# schema_Light_system.net
KiCad netlist of a schematic drawn in EAGLE
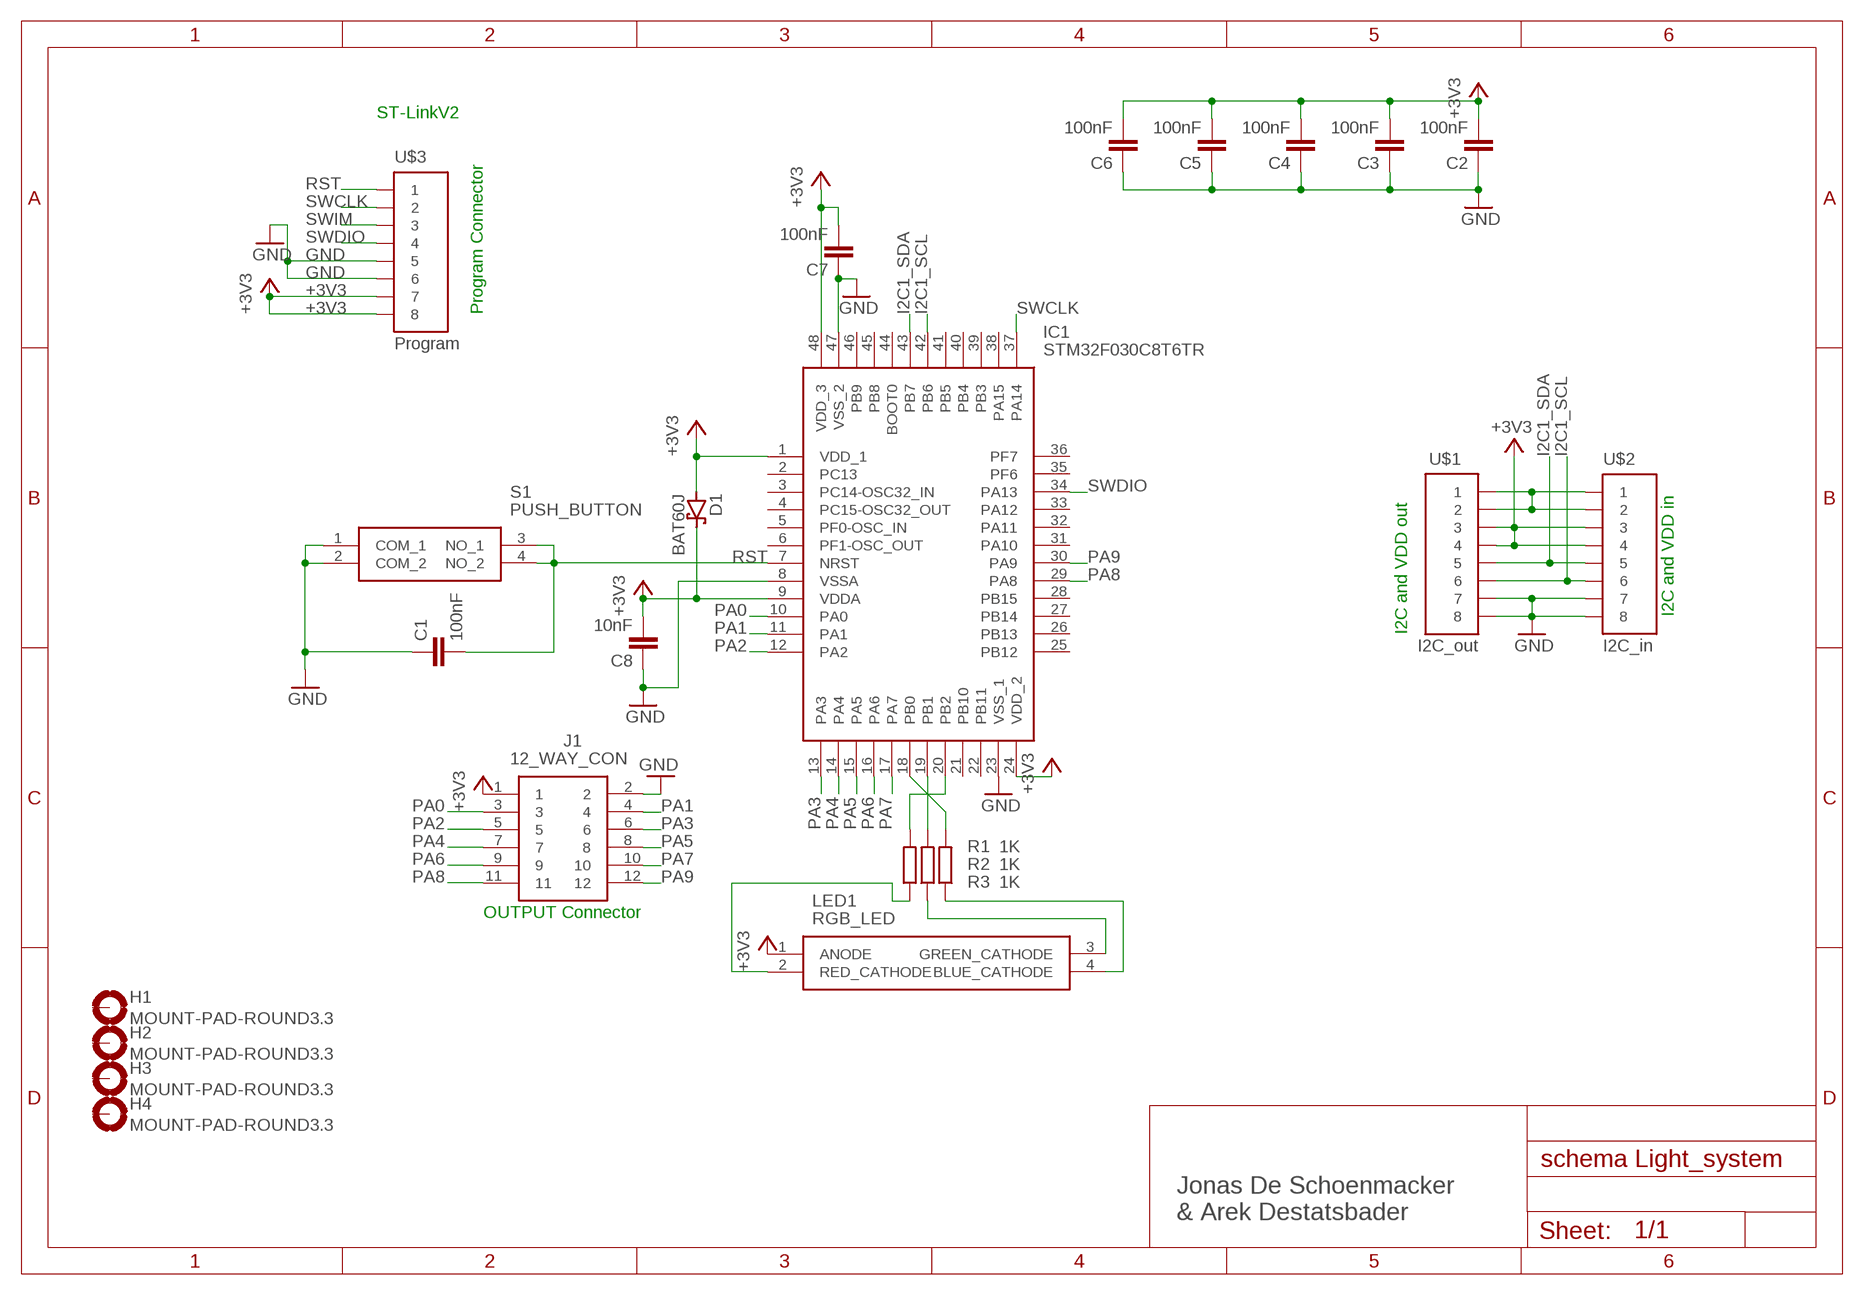
[diagram p0: schematic, sheet 1]

(export (version "E")
  (design (tool "Eeschema 10.0.6"))
  (components
    (comp (ref "C1")
      (value "100nF")
      (footprint "eagle-import:C1206")
      (libsource (lib "eagle-import") (part "C-EUC1206"))
    )
    (comp (ref "C2")
      (value "100nF")
      (footprint "eagle-import:C1206")
      (libsource (lib "eagle-import") (part "C-EUC1206"))
    )
    (comp (ref "C3")
      (value "100nF")
      (footprint "eagle-import:C1206")
      (libsource (lib "eagle-import") (part "C-EUC1206"))
    )
    (comp (ref "C4")
      (value "100nF")
      (footprint "eagle-import:C1206")
      (libsource (lib "eagle-import") (part "C-EUC1206"))
    )
    (comp (ref "C5")
      (value "100nF")
      (footprint "eagle-import:C1206")
      (libsource (lib "eagle-import") (part "C-EUC1206"))
    )
    (comp (ref "C6")
      (value "100nF")
      (footprint "eagle-import:C1206")
      (libsource (lib "eagle-import") (part "C-EUC1206"))
    )
    (comp (ref "C7")
      (value "100nF")
      (footprint "eagle-import:C1206")
      (libsource (lib "eagle-import") (part "C-EUC1206"))
    )
    (comp (ref "C8")
      (value "10nF")
      (footprint "eagle-import:C1206")
      (libsource (lib "eagle-import") (part "C-EUC1206"))
    )
    (comp (ref "D1")
      (value "BAT60J")
      (footprint "eagle-import:SOD323_ST")
      (libsource (lib "eagle-import") (part "BAT60J"))
    )
    (comp (ref "H1")
      (value "MOUNT-PAD-ROUND3.3")
      (footprint "eagle-import:3,3-PAD")
      (libsource (lib "eagle-import") (part "MOUNT-PAD-ROUND3.3"))
    )
    (comp (ref "H2")
      (value "MOUNT-PAD-ROUND3.3")
      (footprint "eagle-import:3,3-PAD")
      (libsource (lib "eagle-import") (part "MOUNT-PAD-ROUND3.3"))
    )
    (comp (ref "H3")
      (value "MOUNT-PAD-ROUND3.3")
      (footprint "eagle-import:3,3-PAD")
      (libsource (lib "eagle-import") (part "MOUNT-PAD-ROUND3.3"))
    )
    (comp (ref "H4")
      (value "MOUNT-PAD-ROUND3.3")
      (footprint "eagle-import:3,3-PAD")
      (libsource (lib "eagle-import") (part "MOUNT-PAD-ROUND3.3"))
    )
    (comp (ref "IC1")
      (value "STM32F030C8T6TR")
      (footprint "eagle-import:QFP50P900X900X160-48N")
      (fields (field (name "MOUSER_PART_NUMBER") "511-STM32F030C8T6TR"))
      (libsource (lib "eagle-import") (part "STM32F030C8T6TR"))
    )
    (comp (ref "J1")
      (value "12_WAY_CON")
      (footprint "eagle-import:1990106")
      (fields
        (field (name "MANUFACTURER_PART_NUMBER") "1990106")
        (field (name "MOUSER_PART_NUMBER") "651-1990106")
      )
      (libsource (lib "eagle-import") (part "12_WAY_CON"))
    )
    (comp (ref "LED1")
      (value "RGB_LED")
      (footprint "eagle-import:ASMBKTF00A306")
      (fields
        (field (name "MANUFACTURER_PART_NUMBER") "ASMB-KTF0-0A306")
        (field (name "MOUSER_PART_NUMBER") "630-ASMB-KTF0-0A306")
      )
      (libsource (lib "eagle-import") (part "RGB_LED"))
    )
    (comp (ref "R1")
      (value "1K")
      (footprint "eagle-import:R1206")
      (libsource (lib "eagle-import") (part "R-EU_R1206"))
    )
    (comp (ref "R2")
      (value "1K")
      (footprint "eagle-import:R1206")
      (libsource (lib "eagle-import") (part "R-EU_R1206"))
    )
    (comp (ref "R3")
      (value "1K")
      (footprint "eagle-import:R1206")
      (libsource (lib "eagle-import") (part "R-EU_R1206"))
    )
    (comp (ref "S1")
      (value "PUSH_BUTTON")
      (footprint "eagle-import:LL3301FF065QJ")
      (fields
        (field (name "MANUFACTURER_PART_NUMBER") "LL3301FF065QJ")
        (field (name "MOUSER_PART_NUMBER") "612-LL3301FF065QJ")
      )
      (libsource (lib "eagle-import") (part "PUSH_BUTTON"))
    )
    (comp (ref "U$1")
      (value "I2C_out")
      (footprint "eagle-import:MA04-2")
      (libsource (lib "eagle-import") (part "MODULARCONNECTOR"))
    )
    (comp (ref "U$2")
      (value "I2C_in")
      (footprint "eagle-import:MA04-2")
      (libsource (lib "eagle-import") (part "MODULARCONNECTOR"))
    )
    (comp (ref "U$3")
      (value "Program")
      (footprint "eagle-import:MA04-2")
      (libsource (lib "eagle-import") (part "MODULARCONNECTOR"))
    )
  )
  (nets
    (net (code "1") (name "+3V3") (class "Default")
      (node (ref "C2") (pin "2") (pinfunction "2_2") (pintype "passive"))
      (node (ref "C3") (pin "2") (pinfunction "2_2") (pintype "passive"))
      (node (ref "C4") (pin "2") (pinfunction "2_2") (pintype "passive"))
      (node (ref "C5") (pin "2") (pinfunction "2_2") (pintype "passive"))
      (node (ref "C6") (pin "2") (pinfunction "2_2") (pintype "passive"))
      (node (ref "C7") (pin "2") (pinfunction "2_2") (pintype "passive"))
      (node (ref "C8") (pin "2") (pinfunction "2_2") (pintype "passive"))
      (node (ref "D1") (pin "A") (pinfunction "A_A") (pintype "passive"))
      (node (ref "D1") (pin "C") (pinfunction "C_C") (pintype "passive"))
      (node (ref "IC1") (pin "1") (pinfunction "VDD_1_1") (pintype "power_in"))
      (node (ref "IC1") (pin "24") (pinfunction "VDD_2_24") (pintype "power_in"))
      (node (ref "IC1") (pin "48") (pinfunction "VDD_3_48") (pintype "power_in"))
      (node (ref "IC1") (pin "9") (pinfunction "VDDA_9") (pintype "power_in"))
      (node (ref "J1") (pin "1") (pinfunction "1_1") (pintype "bidirectional"))
      (node (ref "LED1") (pin "1") (pinfunction "ANODE_1") (pintype "bidirectional"))
      (node (ref "U$1") (pin "3") (pinfunction "3_3") (pintype "input"))
      (node (ref "U$1") (pin "4") (pinfunction "4_4") (pintype "input"))
      (node (ref "U$2") (pin "3") (pinfunction "3_3") (pintype "input"))
      (node (ref "U$2") (pin "4") (pinfunction "4_4") (pintype "input"))
      (node (ref "U$3") (pin "7") (pinfunction "7_7") (pintype "input"))
      (node (ref "U$3") (pin "8") (pinfunction "8_8") (pintype "input"))
    )
    (net (code "2") (name "/I2C1_SCL") (class "Default")
      (node (ref "IC1") (pin "42") (pinfunction "PB6_42") (pintype "bidirectional"))
      (node (ref "U$1") (pin "6") (pinfunction "6_6") (pintype "input"))
      (node (ref "U$2") (pin "6") (pinfunction "6_6") (pintype "input"))
    )
    (net (code "3") (name "/I2C1_SDA") (class "Default")
      (node (ref "IC1") (pin "43") (pinfunction "PB7_43") (pintype "bidirectional"))
      (node (ref "U$1") (pin "5") (pinfunction "5_5") (pintype "input"))
      (node (ref "U$2") (pin "5") (pinfunction "5_5") (pintype "input"))
    )
    (net (code "4") (name "/PA0") (class "Default")
      (node (ref "IC1") (pin "10") (pinfunction "PA0_10") (pintype "bidirectional"))
      (node (ref "J1") (pin "3") (pinfunction "3_3") (pintype "bidirectional"))
    )
    (net (code "5") (name "/PA1") (class "Default")
      (node (ref "IC1") (pin "11") (pinfunction "PA1_11") (pintype "bidirectional"))
      (node (ref "J1") (pin "4") (pinfunction "4_4") (pintype "bidirectional"))
    )
    (net (code "6") (name "/PA2") (class "Default")
      (node (ref "IC1") (pin "12") (pinfunction "PA2_12") (pintype "bidirectional"))
      (node (ref "J1") (pin "5") (pinfunction "5_5") (pintype "bidirectional"))
    )
    (net (code "7") (name "/PA3") (class "Default")
      (node (ref "IC1") (pin "13") (pinfunction "PA3_13") (pintype "bidirectional"))
      (node (ref "J1") (pin "6") (pinfunction "6_6") (pintype "bidirectional"))
    )
    (net (code "8") (name "/PA4") (class "Default")
      (node (ref "IC1") (pin "14") (pinfunction "PA4_14") (pintype "bidirectional"))
      (node (ref "J1") (pin "7") (pinfunction "7_7") (pintype "bidirectional"))
    )
    (net (code "9") (name "/PA5") (class "Default")
      (node (ref "IC1") (pin "15") (pinfunction "PA5_15") (pintype "bidirectional"))
      (node (ref "J1") (pin "8") (pinfunction "8_8") (pintype "bidirectional"))
    )
    (net (code "10") (name "/PA6") (class "Default")
      (node (ref "IC1") (pin "16") (pinfunction "PA6_16") (pintype "bidirectional"))
      (node (ref "J1") (pin "9") (pinfunction "9_9") (pintype "bidirectional"))
    )
    (net (code "11") (name "/PA7") (class "Default")
      (node (ref "IC1") (pin "17") (pinfunction "PA7_17") (pintype "bidirectional"))
      (node (ref "J1") (pin "10") (pinfunction "10_10") (pintype "bidirectional"))
    )
    (net (code "12") (name "/PA8") (class "Default")
      (node (ref "IC1") (pin "29") (pinfunction "PA8_29") (pintype "bidirectional"))
      (node (ref "J1") (pin "11") (pinfunction "11_11") (pintype "bidirectional"))
    )
    (net (code "13") (name "/PA9") (class "Default")
      (node (ref "IC1") (pin "30") (pinfunction "PA9_30") (pintype "bidirectional"))
      (node (ref "J1") (pin "12") (pinfunction "12_12") (pintype "bidirectional"))
    )
    (net (code "14") (name "/RST") (class "Default")
      (node (ref "C1") (pin "2") (pinfunction "2_2") (pintype "passive"))
      (node (ref "IC1") (pin "7") (pinfunction "NRST_7") (pintype "input"))
      (node (ref "S1") (pin "3") (pinfunction "NO_1_3") (pintype "bidirectional"))
      (node (ref "S1") (pin "4") (pinfunction "NO_2_4") (pintype "bidirectional"))
      (node (ref "U$3") (pin "1") (pinfunction "1_1") (pintype "input"))
    )
    (net (code "15") (name "/SWCLK") (class "Default")
      (node (ref "IC1") (pin "37") (pinfunction "PA14_37") (pintype "bidirectional"))
      (node (ref "U$3") (pin "2") (pinfunction "2_2") (pintype "input"))
    )
    (net (code "16") (name "/SWDIO") (class "Default")
      (node (ref "IC1") (pin "34") (pinfunction "PA13_34") (pintype "bidirectional"))
      (node (ref "U$3") (pin "4") (pinfunction "4_4") (pintype "input"))
    )
    (net (code "17") (name "/SWIM") (class "Default")
      (node (ref "U$3") (pin "3") (pinfunction "3_3") (pintype "input"))
    )
    (net (code "18") (name "GND") (class "Default")
      (node (ref "C1") (pin "1") (pinfunction "1_1") (pintype "passive"))
      (node (ref "C2") (pin "1") (pinfunction "1_1") (pintype "passive"))
      (node (ref "C3") (pin "1") (pinfunction "1_1") (pintype "passive"))
      (node (ref "C4") (pin "1") (pinfunction "1_1") (pintype "passive"))
      (node (ref "C5") (pin "1") (pinfunction "1_1") (pintype "passive"))
      (node (ref "C6") (pin "1") (pinfunction "1_1") (pintype "passive"))
      (node (ref "C7") (pin "1") (pinfunction "1_1") (pintype "passive"))
      (node (ref "C8") (pin "1") (pinfunction "1_1") (pintype "passive"))
      (node (ref "IC1") (pin "23") (pinfunction "VSS_1_23") (pintype "power_in"))
      (node (ref "IC1") (pin "47") (pinfunction "VSS_2_47") (pintype "power_in"))
      (node (ref "IC1") (pin "8") (pinfunction "VSSA_8") (pintype "power_in"))
      (node (ref "J1") (pin "2") (pinfunction "2_2") (pintype "bidirectional"))
      (node (ref "S1") (pin "1") (pinfunction "COM_1_1") (pintype "bidirectional"))
      (node (ref "S1") (pin "2") (pinfunction "COM_2_2") (pintype "bidirectional"))
      (node (ref "U$1") (pin "7") (pinfunction "7_7") (pintype "input"))
      (node (ref "U$1") (pin "8") (pinfunction "8_8") (pintype "input"))
      (node (ref "U$2") (pin "7") (pinfunction "7_7") (pintype "input"))
      (node (ref "U$2") (pin "8") (pinfunction "8_8") (pintype "input"))
      (node (ref "U$3") (pin "5") (pinfunction "5_5") (pintype "input"))
      (node (ref "U$3") (pin "6") (pinfunction "6_6") (pintype "input"))
    )
    (net (code "19") (name "Net-(IC1-PB0)") (class "Default")
      (node (ref "IC1") (pin "18") (pinfunction "PB0_18") (pintype "bidirectional"))
      (node (ref "R3") (pin "2") (pinfunction "2_2") (pintype "passive"))
    )
    (net (code "20") (name "Net-(IC1-PB1)") (class "Default")
      (node (ref "IC1") (pin "19") (pinfunction "PB1_19") (pintype "bidirectional"))
      (node (ref "R2") (pin "2") (pinfunction "2_2") (pintype "passive"))
    )
    (net (code "21") (name "Net-(IC1-PB2)") (class "Default")
      (node (ref "IC1") (pin "20") (pinfunction "PB2_20") (pintype "bidirectional"))
      (node (ref "R1") (pin "2") (pinfunction "2_2") (pintype "passive"))
    )
    (net (code "22") (name "Net-(LED1-BLUE_CATHODE)") (class "Default")
      (node (ref "LED1") (pin "4") (pinfunction "BLUE_CATHODE_4") (pintype "bidirectional"))
      (node (ref "R3") (pin "1") (pinfunction "1_1") (pintype "passive"))
    )
    (net (code "23") (name "Net-(LED1-GREEN_CATHODE)") (class "Default")
      (node (ref "LED1") (pin "3") (pinfunction "GREEN_CATHODE_3") (pintype "bidirectional"))
      (node (ref "R2") (pin "1") (pinfunction "1_1") (pintype "passive"))
    )
    (net (code "24") (name "Net-(LED1-RED_CATHODE)") (class "Default")
      (node (ref "LED1") (pin "2") (pinfunction "RED_CATHODE_2") (pintype "bidirectional"))
      (node (ref "R1") (pin "1") (pinfunction "1_1") (pintype "passive"))
    )
    (net (code "25") (name "Net-(U$1-Pad1)") (class "Default")
      (node (ref "U$1") (pin "1") (pinfunction "1_1") (pintype "input"))
      (node (ref "U$1") (pin "2") (pinfunction "2_2") (pintype "input"))
      (node (ref "U$2") (pin "1") (pinfunction "1_1") (pintype "input"))
      (node (ref "U$2") (pin "2") (pinfunction "2_2") (pintype "input"))
    )
    (net (code "26") (name "unconnected-(H1-MOUNT-PadB3,3)") (class "Default")
      (node (ref "H1") (pin "B3,3") (pinfunction "MOUNT_B3,3") (pintype "passive"))
    )
    (net (code "27") (name "unconnected-(H2-MOUNT-PadB3,3)") (class "Default")
      (node (ref "H2") (pin "B3,3") (pinfunction "MOUNT_B3,3") (pintype "passive"))
    )
    (net (code "28") (name "unconnected-(H3-MOUNT-PadB3,3)") (class "Default")
      (node (ref "H3") (pin "B3,3") (pinfunction "MOUNT_B3,3") (pintype "passive"))
    )
    (net (code "29") (name "unconnected-(H4-MOUNT-PadB3,3)") (class "Default")
      (node (ref "H4") (pin "B3,3") (pinfunction "MOUNT_B3,3") (pintype "passive"))
    )
    (net (code "30") (name "unconnected-(IC1-BOOT0-Pad44)") (class "Default")
      (node (ref "IC1") (pin "44") (pinfunction "BOOT0_44") (pintype "bidirectional"))
    )
    (net (code "31") (name "unconnected-(IC1-PA10-Pad31)") (class "Default")
      (node (ref "IC1") (pin "31") (pinfunction "PA10_31") (pintype "bidirectional"))
    )
    (net (code "32") (name "unconnected-(IC1-PA11-Pad32)") (class "Default")
      (node (ref "IC1") (pin "32") (pinfunction "PA11_32") (pintype "bidirectional"))
    )
    (net (code "33") (name "unconnected-(IC1-PA12-Pad33)") (class "Default")
      (node (ref "IC1") (pin "33") (pinfunction "PA12_33") (pintype "bidirectional"))
    )
    (net (code "34") (name "unconnected-(IC1-PA15-Pad38)") (class "Default")
      (node (ref "IC1") (pin "38") (pinfunction "PA15_38") (pintype "bidirectional"))
    )
    (net (code "35") (name "unconnected-(IC1-PB3-Pad39)") (class "Default")
      (node (ref "IC1") (pin "39") (pinfunction "PB3_39") (pintype "bidirectional"))
    )
    (net (code "36") (name "unconnected-(IC1-PB4-Pad40)") (class "Default")
      (node (ref "IC1") (pin "40") (pinfunction "PB4_40") (pintype "bidirectional"))
    )
    (net (code "37") (name "unconnected-(IC1-PB5-Pad41)") (class "Default")
      (node (ref "IC1") (pin "41") (pinfunction "PB5_41") (pintype "bidirectional"))
    )
    (net (code "38") (name "unconnected-(IC1-PB8-Pad45)") (class "Default")
      (node (ref "IC1") (pin "45") (pinfunction "PB8_45") (pintype "bidirectional"))
    )
    (net (code "39") (name "unconnected-(IC1-PB9-Pad46)") (class "Default")
      (node (ref "IC1") (pin "46") (pinfunction "PB9_46") (pintype "bidirectional"))
    )
    (net (code "40") (name "unconnected-(IC1-PB10-Pad21)") (class "Default")
      (node (ref "IC1") (pin "21") (pinfunction "PB10_21") (pintype "bidirectional"))
    )
    (net (code "41") (name "unconnected-(IC1-PB11-Pad22)") (class "Default")
      (node (ref "IC1") (pin "22") (pinfunction "PB11_22") (pintype "bidirectional"))
    )
    (net (code "42") (name "unconnected-(IC1-PB12-Pad25)") (class "Default")
      (node (ref "IC1") (pin "25") (pinfunction "PB12_25") (pintype "bidirectional"))
    )
    (net (code "43") (name "unconnected-(IC1-PB13-Pad26)") (class "Default")
      (node (ref "IC1") (pin "26") (pinfunction "PB13_26") (pintype "bidirectional"))
    )
    (net (code "44") (name "unconnected-(IC1-PB14-Pad27)") (class "Default")
      (node (ref "IC1") (pin "27") (pinfunction "PB14_27") (pintype "bidirectional"))
    )
    (net (code "45") (name "unconnected-(IC1-PB15-Pad28)") (class "Default")
      (node (ref "IC1") (pin "28") (pinfunction "PB15_28") (pintype "bidirectional"))
    )
    (net (code "46") (name "unconnected-(IC1-PC13-Pad2)") (class "Default")
      (node (ref "IC1") (pin "2") (pinfunction "PC13_2") (pintype "bidirectional"))
    )
    (net (code "47") (name "unconnected-(IC1-PC14-OSC32_IN-Pad3)") (class "Default")
      (node (ref "IC1") (pin "3") (pinfunction "PC14-OSC32_IN_3") (pintype "input"))
    )
    (net (code "48") (name "unconnected-(IC1-PC15-OSC32_OUT-Pad4)") (class "Default")
      (node (ref "IC1") (pin "4") (pinfunction "PC15-OSC32_OUT_4") (pintype "output"))
    )
    (net (code "49") (name "unconnected-(IC1-PF0-OSC_IN-Pad5)") (class "Default")
      (node (ref "IC1") (pin "5") (pinfunction "PF0-OSC_IN_5") (pintype "input"))
    )
    (net (code "50") (name "unconnected-(IC1-PF1-OSC_OUT-Pad6)") (class "Default")
      (node (ref "IC1") (pin "6") (pinfunction "PF1-OSC_OUT_6") (pintype "output"))
    )
    (net (code "51") (name "unconnected-(IC1-PF6-Pad35)") (class "Default")
      (node (ref "IC1") (pin "35") (pinfunction "PF6_35") (pintype "bidirectional"))
    )
    (net (code "52") (name "unconnected-(IC1-PF7-Pad36)") (class "Default")
      (node (ref "IC1") (pin "36") (pinfunction "PF7_36") (pintype "bidirectional"))
    )
  )
)
